# DAC.net
KiCad netlist of a schematic drawn in EAGLE
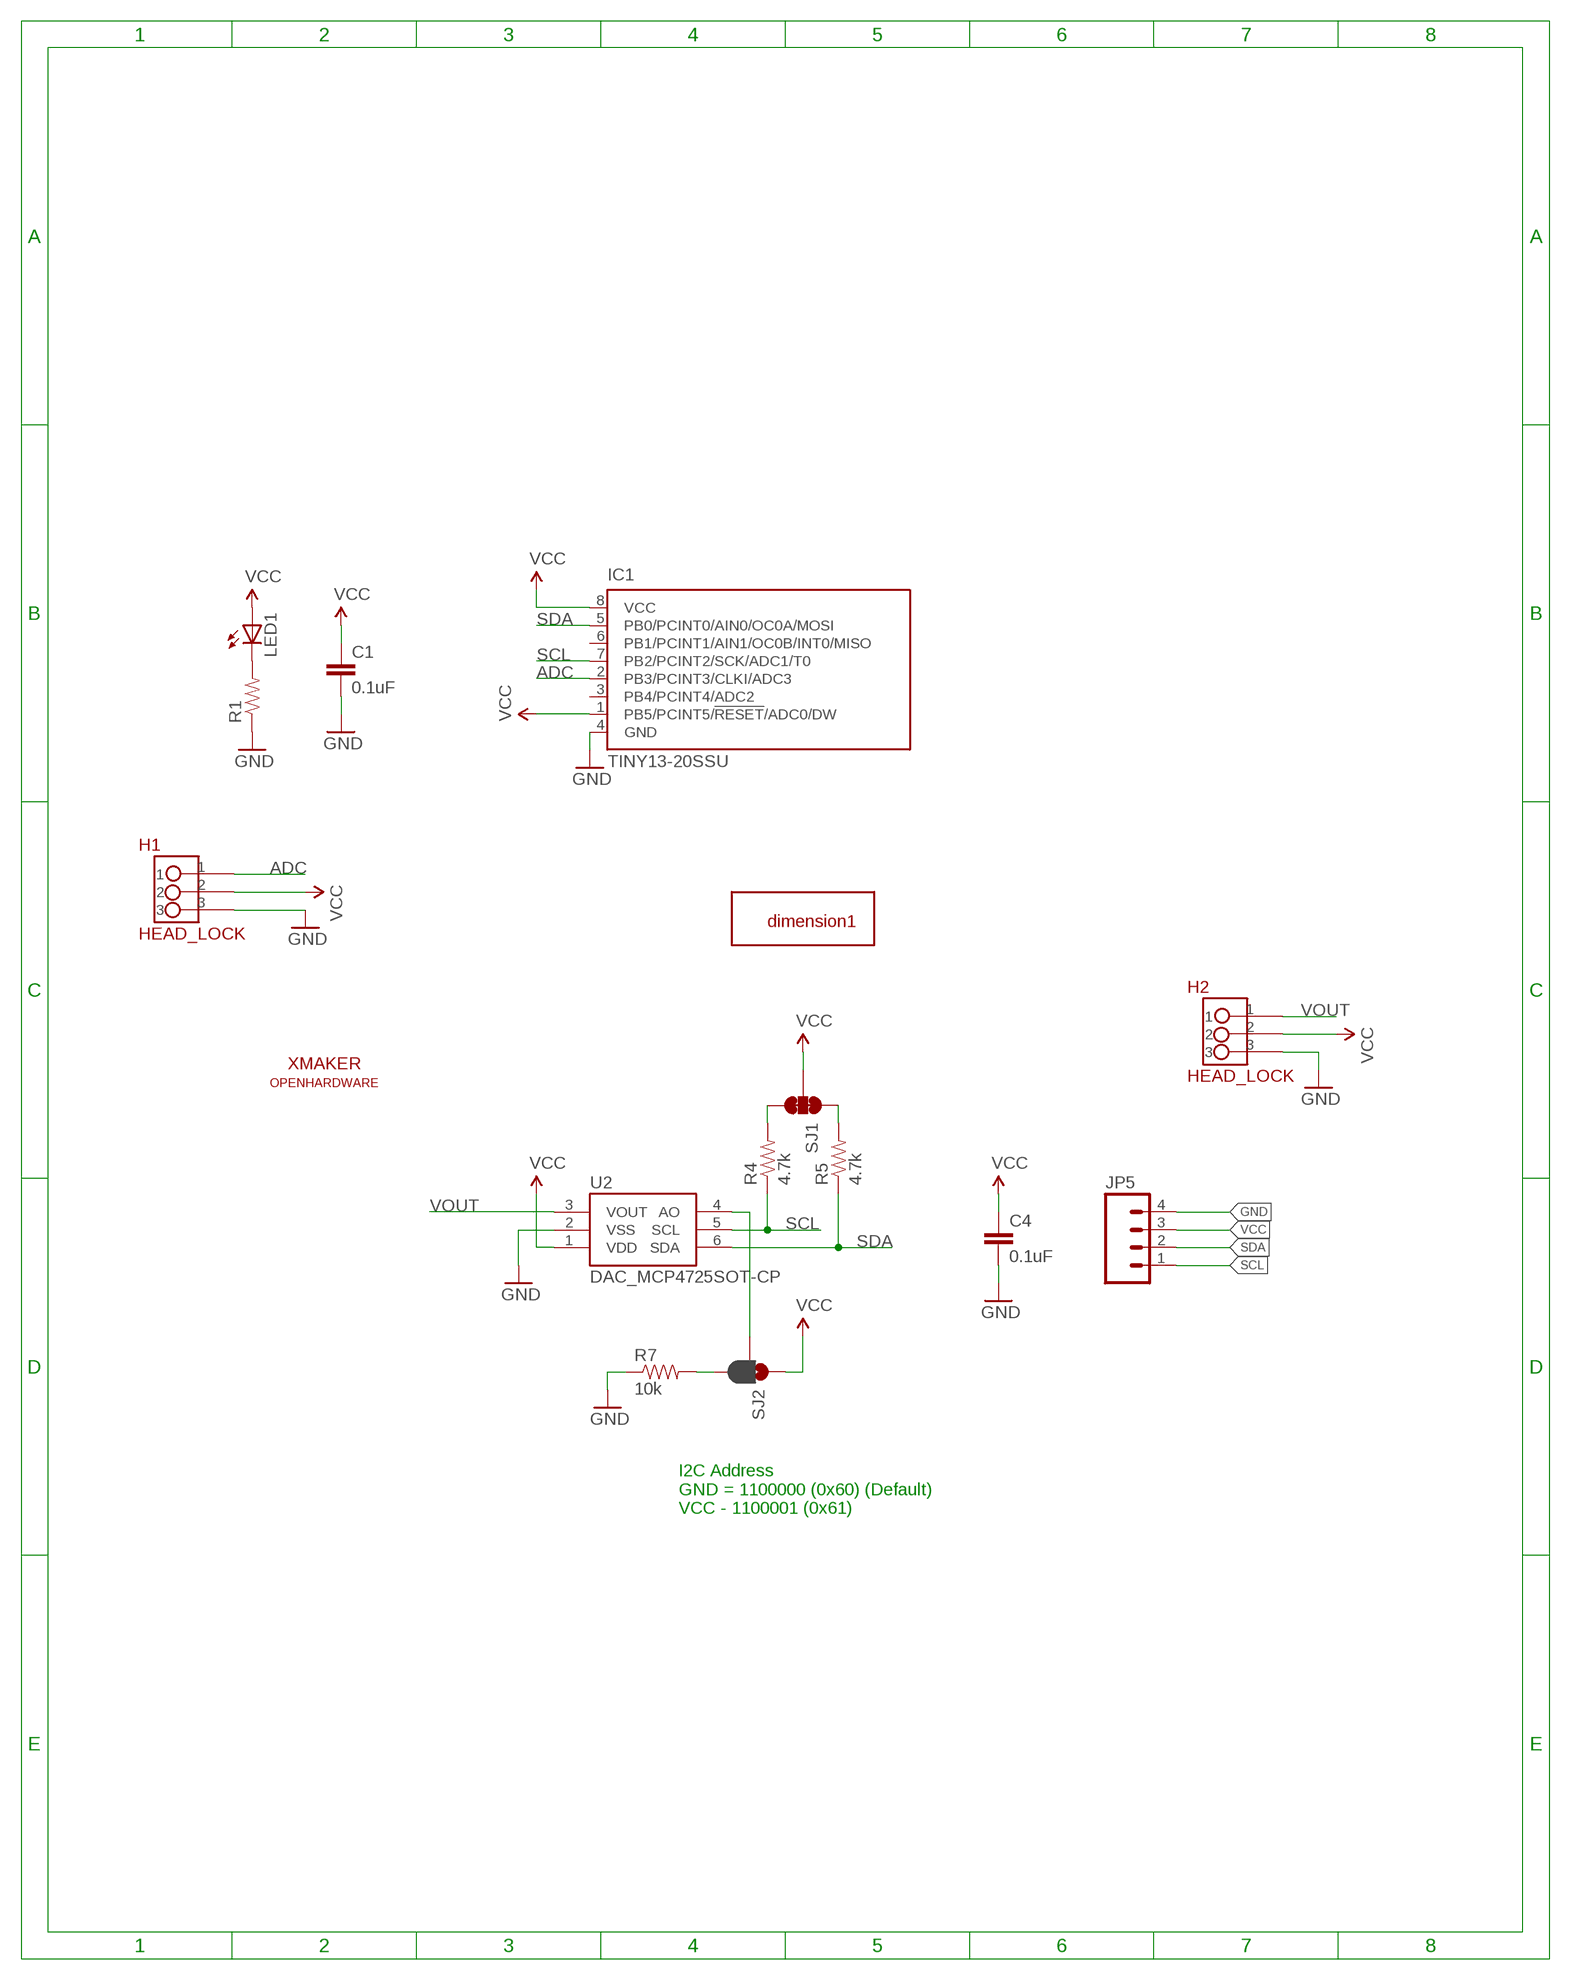
[diagram p0: schematic, sheet 1]

(export (version "E")
  (design (tool "Eeschema 10.0.6"))
  (components
    (comp (ref "C1")
      (value "0.1uF")
      (footprint "eagle-import:0603-CAP")
      (libsource (lib "eagle-import") (part "CAP0603-CAP"))
    )
    (comp (ref "C4")
      (value "0.1uF")
      (footprint "eagle-import:0603-CAP")
      (libsource (lib "eagle-import") (part "CAP0603-CAP"))
    )
    (comp (ref "H1")
      (value "HEAD_LOCK")
      (footprint "eagle-import:HEAD_LOCK")
      (libsource (lib "eagle-import") (part "HEAD_LOCK"))
    )
    (comp (ref "H2")
      (value "HEAD_LOCK")
      (footprint "eagle-import:HEAD_LOCK")
      (libsource (lib "eagle-import") (part "HEAD_LOCK"))
    )
    (comp (ref "IC1")
      (value "TINY13-20SSU")
      (footprint "eagle-import:8S1")
      (fields (field (name "MPN") "ATTINY13-20SSU"))
      (libsource (lib "eagle-import") (part "TINY13SSU-20"))
    )
    (comp (ref "JP5")
      (value "M04PTH")
      (footprint "eagle-import:1X04")
      (libsource (lib "eagle-import") (part "M04PTH"))
    )
    (comp (ref "LED1")
      (value "LEDSML0603")
      (footprint "eagle-import:SML0603")
      (libsource (lib "eagle-import") (part "LEDSML0603"))
    )
    (comp (ref "R1")
      (value "RESISTOR0603-RES")
      (footprint "eagle-import:0603-RES")
      (libsource (lib "eagle-import") (part "SparkFun-Passives_RESISTOR0603-RES"))
    )
    (comp (ref "R4")
      (value "4.7k")
      (footprint "eagle-import:0603-RES")
      (libsource (lib "eagle-import") (part "RESISTOR0603-RES"))
    )
    (comp (ref "R5")
      (value "4.7k")
      (footprint "eagle-import:0603-RES")
      (libsource (lib "eagle-import") (part "RESISTOR0603-RES"))
    )
    (comp (ref "R7")
      (value "10k")
      (footprint "eagle-import:0603-RES")
      (libsource (lib "eagle-import") (part "RESISTOR0603-RES"))
    )
    (comp (ref "SJ1")
      (value "JUMPER-PAD-3-NC_BY_TRACE")
      (footprint "eagle-import:PAD-JUMPER-3-3OF3_NC_BY_TRACE_YES_SILK_FULL_BOX")
      (libsource (lib "eagle-import") (part "JUMPER-PAD-3-NC_BY_TRACE"))
    )
    (comp (ref "SJ2")
      (value "JUMPER-PAD-3-2OF3_NC_BY_PASTE")
      (footprint "eagle-import:PAD-JUMPER-3-2OF3_NC_BY_PASTE_YES_SILK_FULL_BOX")
      (libsource (lib "eagle-import") (part "JUMPER-PAD-3-2OF3_NC_BY_PASTE"))
    )
    (comp (ref "U$1")
      (value "XMAKERLOGO2")
      (footprint "eagle-import:XMAKERLOGO2")
      (libsource (lib "eagle-import") (part "XMAKERLOGO2"))
    )
    (comp (ref "U$2")
      (value "DIMENSION1")
      (footprint "eagle-import:DIMENSION1")
      (libsource (lib "eagle-import") (part "DIMENSION1"))
    )
    (comp (ref "U$3")
      (value "OPENHARDWARE")
      (footprint "eagle-import:OPENHARDWARE")
      (libsource (lib "eagle-import") (part "OPENHARDWARE"))
    )
    (comp (ref "U2")
      (value "DAC_MCP4725SOT-CP")
      (footprint "eagle-import:SOT23-6-MCP4725")
      (libsource (lib "eagle-import") (part "DAC_MCP4725SOT-CP"))
    )
  )
  (nets
    (net (code "1") (name "/ADC") (class "Default")
      (node (ref "H1") (pin "1") (pinfunction "1_1") (pintype "passive"))
      (node (ref "IC1") (pin "2") (pinfunction "PB3/PCINT3/CLKI/ADC3_2") (pintype "bidirectional"))
    )
    (net (code "2") (name "/VOUT") (class "Default")
      (node (ref "H2") (pin "1") (pinfunction "1_1") (pintype "passive"))
      (node (ref "U2") (pin "3") (pinfunction "VOUT_3") (pintype "bidirectional"))
    )
    (net (code "3") (name "GND") (class "Default")
      (node (ref "C1") (pin "2") (pinfunction "2_2") (pintype "passive"))
      (node (ref "C4") (pin "2") (pinfunction "2_2") (pintype "passive"))
      (node (ref "H1") (pin "3") (pinfunction "3_3") (pintype "passive"))
      (node (ref "H2") (pin "3") (pinfunction "3_3") (pintype "passive"))
      (node (ref "IC1") (pin "4") (pinfunction "GND_4") (pintype "power_in"))
      (node (ref "JP5") (pin "4") (pinfunction "4_4") (pintype "passive"))
      (node (ref "R1") (pin "1") (pinfunction "1_1") (pintype "passive"))
      (node (ref "R7") (pin "1") (pinfunction "1_1") (pintype "passive"))
      (node (ref "U2") (pin "2") (pinfunction "VSS_2") (pintype "bidirectional"))
    )
    (net (code "4") (name "Net-(LED1-PadC)") (class "Default")
      (node (ref "LED1") (pin "C") (pinfunction "C_C") (pintype "passive"))
      (node (ref "R1") (pin "2") (pinfunction "2_2") (pintype "passive"))
    )
    (net (code "5") (name "Net-(R4-Pad2)") (class "Default")
      (node (ref "R4") (pin "2") (pinfunction "2_2") (pintype "passive"))
      (node (ref "SJ1") (pin "3") (pinfunction "3_3") (pintype "passive"))
    )
    (net (code "6") (name "Net-(R5-Pad2)") (class "Default")
      (node (ref "R5") (pin "2") (pinfunction "2_2") (pintype "passive"))
      (node (ref "SJ1") (pin "1") (pinfunction "1_1") (pintype "passive"))
    )
    (net (code "7") (name "Net-(R7-Pad2)") (class "Default")
      (node (ref "R7") (pin "2") (pinfunction "2_2") (pintype "passive"))
      (node (ref "SJ2") (pin "3") (pinfunction "3_3") (pintype "passive"))
    )
    (net (code "8") (name "Net-(U2-AO)") (class "Default")
      (node (ref "SJ2") (pin "2") (pinfunction "2_2") (pintype "passive"))
      (node (ref "U2") (pin "4") (pinfunction "AO_4") (pintype "bidirectional"))
    )
    (net (code "9") (name "SCL") (class "Default")
      (node (ref "IC1") (pin "7") (pinfunction "PB2/PCINT2/SCK/ADC1/T0_7") (pintype "bidirectional"))
      (node (ref "JP5") (pin "1") (pinfunction "1_1") (pintype "passive"))
      (node (ref "R4") (pin "1") (pinfunction "1_1") (pintype "passive"))
      (node (ref "U2") (pin "5") (pinfunction "SCL_5") (pintype "bidirectional"))
    )
    (net (code "10") (name "SDA") (class "Default")
      (node (ref "IC1") (pin "5") (pinfunction "PB0/PCINT0/AIN0/OC0A/MOSI_5") (pintype "bidirectional"))
      (node (ref "JP5") (pin "2") (pinfunction "2_2") (pintype "passive"))
      (node (ref "R5") (pin "1") (pinfunction "1_1") (pintype "passive"))
      (node (ref "U2") (pin "6") (pinfunction "SDA_6") (pintype "bidirectional"))
    )
    (net (code "11") (name "VCC") (class "Default")
      (node (ref "C1") (pin "1") (pinfunction "1_1") (pintype "passive"))
      (node (ref "C4") (pin "1") (pinfunction "1_1") (pintype "passive"))
      (node (ref "H1") (pin "2") (pinfunction "2_2") (pintype "passive"))
      (node (ref "H2") (pin "2") (pinfunction "2_2") (pintype "passive"))
      (node (ref "IC1") (pin "1") (pinfunction "PB5/PCINT5/~{RESET}/ADC0/DW_1") (pintype "bidirectional"))
      (node (ref "IC1") (pin "8") (pinfunction "VCC_8") (pintype "power_in"))
      (node (ref "JP5") (pin "3") (pinfunction "3_3") (pintype "passive"))
      (node (ref "LED1") (pin "A") (pinfunction "A_A") (pintype "passive"))
      (node (ref "SJ1") (pin "2") (pinfunction "2_2") (pintype "passive"))
      (node (ref "SJ2") (pin "1") (pinfunction "1_1") (pintype "passive"))
      (node (ref "U2") (pin "1") (pinfunction "VDD_1") (pintype "bidirectional"))
    )
    (net (code "12") (name "unconnected-(IC1-PB1{slash}PCINT1{slash}AIN1{slash}OC0B{slash}INT0{slash}MISO-Pad6)") (class "Default")
      (node (ref "IC1") (pin "6") (pinfunction "PB1/PCINT1/AIN1/OC0B/INT0/MISO_6") (pintype "bidirectional"))
    )
    (net (code "13") (name "unconnected-(IC1-PB4{slash}PCINT4{slash}ADC2-Pad3)") (class "Default")
      (node (ref "IC1") (pin "3") (pinfunction "PB4/PCINT4/ADC2_3") (pintype "bidirectional"))
    )
  )
)
